# tdo_frontend.net
KiCad netlist of a schematic drawn in EAGLE
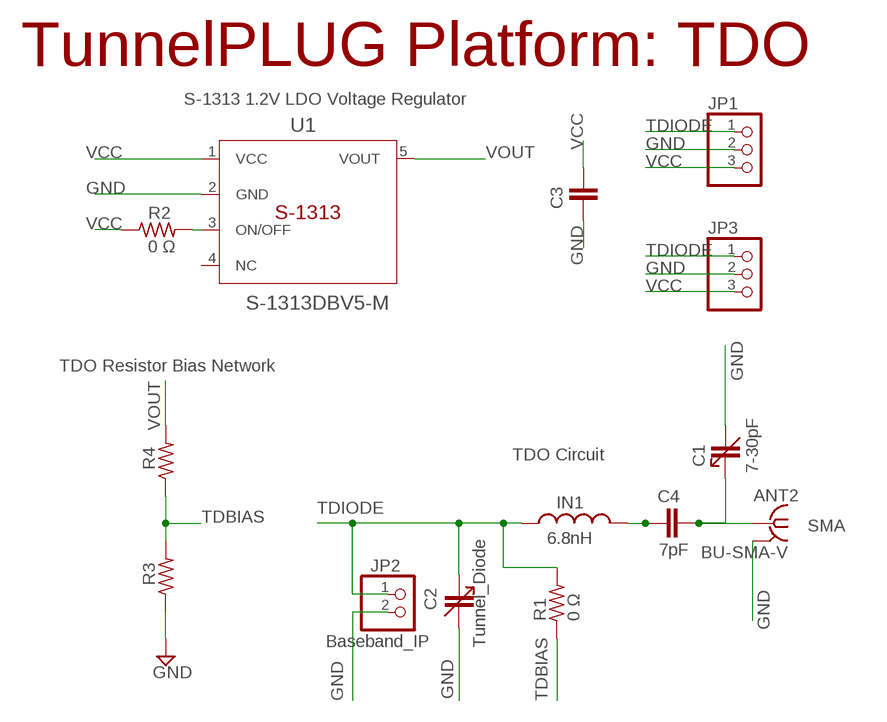
[diagram p0: schematic, sheet 1]

(export (version "E")
  (design (tool "Eeschema 10.0.6"))
  (components
    (comp (ref "C1")
      (value "7-30pF")
      (footprint "eagle-import:CTZ3")
      (libsource (lib "eagle-import") (part "CAP_ADJSMD"))
    )
    (comp (ref "C2")
      (value "7-30pF")
      (footprint "eagle-import:CTZ3")
      (libsource (lib "eagle-import") (part "CAP_ADJSMD"))
    )
    (comp (ref "C3")
      (value "CAPACITOR")
      (footprint "eagle-import:C0603")
      (libsource (lib "eagle-import") (part "CAPACITOR"))
    )
    (comp (ref "C4")
      (value "7pF")
      (footprint "eagle-import:C0603")
      (libsource (lib "eagle-import") (part "CAPACITOR"))
    )
    (comp (ref "IN1")
      (value "6.8nH")
      (footprint "eagle-import:0603_1PRIMARY")
      (libsource (lib "eagle-import") (part "0603_1"))
    )
    (comp (ref "JP1")
      (value "PINHD-1X3/90")
      (footprint "eagle-import:1X03_90")
      (libsource (lib "eagle-import") (part "PINHD-1X3/90"))
    )
    (comp (ref "JP2")
      (value "Baseband_IP")
      (footprint "eagle-import:1X02")
      (libsource (lib "eagle-import") (part "PINHD-1X2/LONG"))
    )
    (comp (ref "JP3")
      (value "PINHD-1X3/LONG")
      (footprint "eagle-import:1X03")
      (libsource (lib "eagle-import") (part "PINHD-1X3/LONG"))
    )
    (comp (ref "R1")
      (value "0 Ω")
      (footprint "eagle-import:R0603")
      (libsource (lib "eagle-import") (part "R-US_R0603"))
    )
    (comp (ref "R2")
      (value "0 Ω")
      (footprint "eagle-import:R0603")
      (libsource (lib "eagle-import") (part "R-US_R0603"))
    )
    (comp (ref "R3")
      (value "R-US_R0603")
      (footprint "eagle-import:R0603")
      (libsource (lib "eagle-import") (part "R-US_R0603"))
    )
    (comp (ref "R4")
      (value "R-US_R0603")
      (footprint "eagle-import:R0603")
      (libsource (lib "eagle-import") (part "R-US_R0603"))
    )
    (comp (ref "SMA")
      (value "BU-SMA-V")
      (footprint "eagle-import:BU-SMA-V")
      (libsource (lib "eagle-import") (part "BU-SMA-V"))
    )
    (comp (ref "U1")
      (value "S-1313DBV5-M")
      (footprint "eagle-import:DBV5-M")
      (fields
        (field (name "GENERIC_PART_NUMBER") "SN74LVC1G32-Q1")
        (field (name "MANUFACTURER") "Texas Instruments")
        (field (name "MANUFACTURER_PART_NUMBER") "SN74LVC1G32QDBVRQ1")
      )
      (libsource (lib "eagle-import") (part "S-1313DBV5-M"))
    )
  )
  (nets
    (net (code "1") (name "/ANT2") (class "Default")
      (node (ref "C1") (pin "+") (pinfunction "3_+") (pintype "passive"))
      (node (ref "C4") (pin "2") (pinfunction "2_2") (pintype "passive"))
      (node (ref "SMA") (pin "1") (pinfunction "1_1") (pintype "passive"))
    )
    (net (code "2") (name "/TDBIAS") (class "Default")
      (node (ref "R1") (pin "1") (pinfunction "1_1") (pintype "passive"))
      (node (ref "R3") (pin "2") (pinfunction "2_2") (pintype "passive"))
      (node (ref "R4") (pin "1") (pinfunction "1_1") (pintype "passive"))
    )
    (net (code "3") (name "/TDIODE") (class "Default")
      (node (ref "C2") (pin "+") (pinfunction "3_+") (pintype "passive"))
      (node (ref "IN1") (pin "1") (pinfunction "1_1") (pintype "passive"))
      (node (ref "JP1") (pin "1") (pinfunction "1_1") (pintype "passive"))
      (node (ref "JP2") (pin "1") (pinfunction "1_1") (pintype "passive"))
      (node (ref "JP3") (pin "1") (pinfunction "1_1") (pintype "passive"))
      (node (ref "R1") (pin "2") (pinfunction "2_2") (pintype "passive"))
    )
    (net (code "4") (name "/VCC") (class "Default")
      (node (ref "C3") (pin "2") (pinfunction "2_2") (pintype "passive"))
      (node (ref "JP1") (pin "3") (pinfunction "3_3") (pintype "passive"))
      (node (ref "JP3") (pin "3") (pinfunction "3_3") (pintype "passive"))
      (node (ref "R2") (pin "1") (pinfunction "1_1") (pintype "passive"))
      (node (ref "U1") (pin "1") (pinfunction "VCC_1") (pintype "power_in"))
    )
    (net (code "5") (name "/VOUT") (class "Default")
      (node (ref "R4") (pin "2") (pinfunction "2_2") (pintype "passive"))
      (node (ref "U1") (pin "5") (pinfunction "VOUT_5") (pintype "power_in"))
    )
    (net (code "6") (name "GND") (class "Default")
      (node (ref "C1") (pin "-") (pinfunction "4_-") (pintype "passive"))
      (node (ref "C2") (pin "-") (pinfunction "4_-") (pintype "passive"))
      (node (ref "C3") (pin "1") (pinfunction "1_1") (pintype "passive"))
      (node (ref "JP1") (pin "2") (pinfunction "2_2") (pintype "passive"))
      (node (ref "JP2") (pin "2") (pinfunction "2_2") (pintype "passive"))
      (node (ref "JP3") (pin "2") (pinfunction "2_2") (pintype "passive"))
      (node (ref "R3") (pin "1") (pinfunction "1_1") (pintype "passive"))
      (node (ref "SMA") (pin "2") (pinfunction "2_2") (pintype "passive"))
      (node (ref "SMA") (pin "3") (pinfunction "2_3") (pintype "passive"))
      (node (ref "SMA") (pin "4") (pinfunction "2_4") (pintype "passive"))
      (node (ref "SMA") (pin "5") (pinfunction "2_5") (pintype "passive"))
      (node (ref "U1") (pin "2") (pinfunction "GND_2") (pintype "power_in"))
    )
    (net (code "7") (name "Net-(C4-Pad1)") (class "Default")
      (node (ref "C4") (pin "1") (pinfunction "1_1") (pintype "passive"))
      (node (ref "IN1") (pin "2") (pinfunction "2_2") (pintype "passive"))
    )
    (net (code "8") (name "Net-(U1-ON{slash}OFF)") (class "Default")
      (node (ref "R2") (pin "2") (pinfunction "2_2") (pintype "passive"))
      (node (ref "U1") (pin "3") (pinfunction "ON/OFF_3") (pintype "input"))
    )
    (net (code "9") (name "unconnected-(U1-NC-Pad4)") (class "Default")
      (node (ref "U1") (pin "4") (pinfunction "NC_4") (pintype "input"))
    )
  )
)
